# Sheet1.net
KiCad netlist of a schematic drawn in Altium Designer
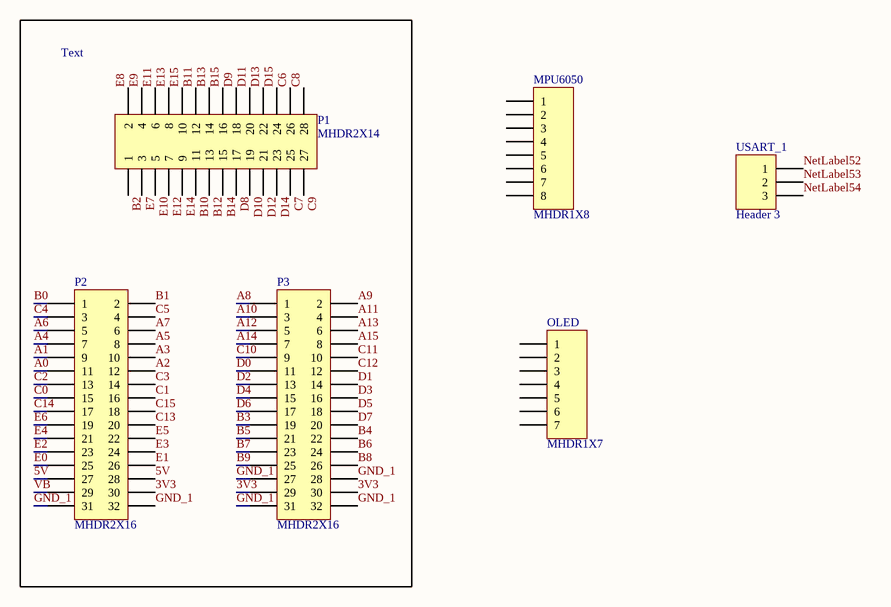
[diagram p0: Sheet1.SchDoc]

(export (version "E")
  (design (tool "Eeschema 10.0.6"))
  (components
    (comp (ref "MPU6050")
      (value "MHDR1X8")
      (footprint "MHDR1X8")
      (description "Header, 8-Pin")
      (fields (field (name "PUBLISHER") "Altium Limited"))
      (libsource (lib "Miscellaneous Connectors") (part "MHDR1X8"))
    )
    (comp (ref "OLED")
      (value "MHDR1X7")
      (footprint "MHDR1X7")
      (description "Header, 7-Pin")
      (fields (field (name "PUBLISHER") "Altium Limited"))
      (libsource (lib "Miscellaneous Connectors") (part "MHDR1X7"))
    )
    (comp (ref "P1")
      (value "MHDR2X14")
      (footprint "MHDR2X14")
      (description "Header, 14-Pin, Dual row")
      (fields (field (name "PUBLISHER") "Altium Limited"))
      (libsource (lib "Miscellaneous Connectors") (part "MHDR2X14"))
    )
    (comp (ref "P2")
      (value "MHDR2X16")
      (footprint "MHDR2X16")
      (description "Header, 16-Pin, Dual row")
      (fields (field (name "PUBLISHER") "Altium Limited"))
      (libsource (lib "Miscellaneous Connectors") (part "MHDR2X16"))
    )
    (comp (ref "P3")
      (value "MHDR2X16")
      (footprint "MHDR2X16")
      (description "Header, 16-Pin, Dual row")
      (fields (field (name "PUBLISHER") "Altium Limited"))
      (libsource (lib "Miscellaneous Connectors") (part "MHDR2X16"))
    )
    (comp (ref "USART_1")
      (value "Header 3")
      (footprint "HDR1X3")
      (description "Header, 3-Pin")
      (fields (field (name "PUBLISHER") "Altium Limited"))
      (libsource (lib "Miscellaneous Connectors") (part "Header 3"))
    )
  )
  (nets
    (net (code "1") (name "/3V3") (class "Default")
      (node (ref "P2") (pin "30") (pinfunction "30_30") (pintype "passive"))
      (node (ref "P3") (pin "29") (pinfunction "29_29") (pintype "passive"))
      (node (ref "P3") (pin "30") (pinfunction "30_30") (pintype "passive"))
    )
    (net (code "2") (name "/5V") (class "Default")
      (node (ref "P2") (pin "27") (pinfunction "27_27") (pintype "passive"))
      (node (ref "P2") (pin "28") (pinfunction "28_28") (pintype "passive"))
    )
    (net (code "3") (name "/A0") (class "Default")
      (node (ref "P2") (pin "11") (pinfunction "11_11") (pintype "passive"))
    )
    (net (code "4") (name "/A1") (class "Default")
      (node (ref "P2") (pin "9") (pinfunction "9_9") (pintype "passive"))
    )
    (net (code "5") (name "/A2") (class "Default")
      (node (ref "P2") (pin "12") (pinfunction "12_12") (pintype "passive"))
    )
    (net (code "6") (name "/A3") (class "Default")
      (node (ref "P2") (pin "10") (pinfunction "10_10") (pintype "passive"))
    )
    (net (code "7") (name "/A4") (class "Default")
      (node (ref "P2") (pin "7") (pinfunction "7_7") (pintype "passive"))
    )
    (net (code "8") (name "/A5") (class "Default")
      (node (ref "P2") (pin "8") (pinfunction "8_8") (pintype "passive"))
    )
    (net (code "9") (name "/A6") (class "Default")
      (node (ref "P2") (pin "5") (pinfunction "5_5") (pintype "passive"))
    )
    (net (code "10") (name "/A7") (class "Default")
      (node (ref "P2") (pin "6") (pinfunction "6_6") (pintype "passive"))
    )
    (net (code "11") (name "/A8") (class "Default")
      (node (ref "P3") (pin "1") (pinfunction "1_1") (pintype "passive"))
    )
    (net (code "12") (name "/A9") (class "Default")
      (node (ref "P3") (pin "2") (pinfunction "2_2") (pintype "passive"))
    )
    (net (code "13") (name "/A10") (class "Default")
      (node (ref "P3") (pin "3") (pinfunction "3_3") (pintype "passive"))
    )
    (net (code "14") (name "/A11") (class "Default")
      (node (ref "P3") (pin "4") (pinfunction "4_4") (pintype "passive"))
    )
    (net (code "15") (name "/A12") (class "Default")
      (node (ref "P3") (pin "5") (pinfunction "5_5") (pintype "passive"))
    )
    (net (code "16") (name "/A13") (class "Default")
      (node (ref "P3") (pin "6") (pinfunction "6_6") (pintype "passive"))
    )
    (net (code "17") (name "/A14") (class "Default")
      (node (ref "P3") (pin "7") (pinfunction "7_7") (pintype "passive"))
    )
    (net (code "18") (name "/A15") (class "Default")
      (node (ref "P3") (pin "8") (pinfunction "8_8") (pintype "passive"))
    )
    (net (code "19") (name "/B0") (class "Default")
      (node (ref "P2") (pin "1") (pinfunction "1_1") (pintype "passive"))
    )
    (net (code "20") (name "/B1") (class "Default")
      (node (ref "P2") (pin "2") (pinfunction "2_2") (pintype "passive"))
    )
    (net (code "21") (name "/B2") (class "Default")
      (node (ref "P1") (pin "1") (pinfunction "1_1") (pintype "passive"))
    )
    (net (code "22") (name "/B3") (class "Default")
      (node (ref "P3") (pin "19") (pinfunction "19_19") (pintype "passive"))
    )
    (net (code "23") (name "/B4") (class "Default")
      (node (ref "P3") (pin "22") (pinfunction "22_22") (pintype "passive"))
    )
    (net (code "24") (name "/B5") (class "Default")
      (node (ref "P3") (pin "21") (pinfunction "21_21") (pintype "passive"))
    )
    (net (code "25") (name "/B6") (class "Default")
      (node (ref "P3") (pin "24") (pinfunction "24_24") (pintype "passive"))
    )
    (net (code "26") (name "/B7") (class "Default")
      (node (ref "P3") (pin "23") (pinfunction "23_23") (pintype "passive"))
    )
    (net (code "27") (name "/B8") (class "Default")
      (node (ref "P3") (pin "26") (pinfunction "26_26") (pintype "passive"))
    )
    (net (code "28") (name "/B9") (class "Default")
      (node (ref "P3") (pin "25") (pinfunction "25_25") (pintype "passive"))
    )
    (net (code "29") (name "/B10") (class "Default")
      (node (ref "P1") (pin "11") (pinfunction "11_11") (pintype "passive"))
    )
    (net (code "30") (name "/B11") (class "Default")
      (node (ref "P1") (pin "12") (pinfunction "12_12") (pintype "passive"))
    )
    (net (code "31") (name "/B12") (class "Default")
      (node (ref "P1") (pin "13") (pinfunction "13_13") (pintype "passive"))
    )
    (net (code "32") (name "/B13") (class "Default")
      (node (ref "P1") (pin "14") (pinfunction "14_14") (pintype "passive"))
    )
    (net (code "33") (name "/B14") (class "Default")
      (node (ref "P1") (pin "15") (pinfunction "15_15") (pintype "passive"))
    )
    (net (code "34") (name "/B15") (class "Default")
      (node (ref "P1") (pin "16") (pinfunction "16_16") (pintype "passive"))
    )
    (net (code "35") (name "/C0") (class "Default")
      (node (ref "P2") (pin "15") (pinfunction "15_15") (pintype "passive"))
    )
    (net (code "36") (name "/C1") (class "Default")
      (node (ref "P2") (pin "16") (pinfunction "16_16") (pintype "passive"))
    )
    (net (code "37") (name "/C2") (class "Default")
      (node (ref "P2") (pin "13") (pinfunction "13_13") (pintype "passive"))
    )
    (net (code "38") (name "/C3") (class "Default")
      (node (ref "P2") (pin "14") (pinfunction "14_14") (pintype "passive"))
    )
    (net (code "39") (name "/C4") (class "Default")
      (node (ref "P2") (pin "3") (pinfunction "3_3") (pintype "passive"))
    )
    (net (code "40") (name "/C5") (class "Default")
      (node (ref "P2") (pin "4") (pinfunction "4_4") (pintype "passive"))
    )
    (net (code "41") (name "/C6") (class "Default")
      (node (ref "P1") (pin "26") (pinfunction "26_26") (pintype "passive"))
    )
    (net (code "42") (name "/C7") (class "Default")
      (node (ref "P1") (pin "25") (pinfunction "25_25") (pintype "passive"))
    )
    (net (code "43") (name "/C8") (class "Default")
      (node (ref "P1") (pin "28") (pinfunction "28_28") (pintype "passive"))
    )
    (net (code "44") (name "/C9") (class "Default")
      (node (ref "P1") (pin "27") (pinfunction "27_27") (pintype "passive"))
    )
    (net (code "45") (name "/C10") (class "Default")
      (node (ref "P3") (pin "9") (pinfunction "9_9") (pintype "passive"))
    )
    (net (code "46") (name "/C11") (class "Default")
      (node (ref "P3") (pin "10") (pinfunction "10_10") (pintype "passive"))
    )
    (net (code "47") (name "/C12") (class "Default")
      (node (ref "P3") (pin "12") (pinfunction "12_12") (pintype "passive"))
    )
    (net (code "48") (name "/C13") (class "Default")
      (node (ref "P2") (pin "20") (pinfunction "20_20") (pintype "passive"))
    )
    (net (code "49") (name "/C14") (class "Default")
      (node (ref "P2") (pin "17") (pinfunction "17_17") (pintype "passive"))
    )
    (net (code "50") (name "/C15") (class "Default")
      (node (ref "P2") (pin "18") (pinfunction "18_18") (pintype "passive"))
    )
    (net (code "51") (name "/D0") (class "Default")
      (node (ref "P3") (pin "11") (pinfunction "11_11") (pintype "passive"))
    )
    (net (code "52") (name "/D1") (class "Default")
      (node (ref "P3") (pin "14") (pinfunction "14_14") (pintype "passive"))
    )
    (net (code "53") (name "/D2") (class "Default")
      (node (ref "P3") (pin "13") (pinfunction "13_13") (pintype "passive"))
    )
    (net (code "54") (name "/D3") (class "Default")
      (node (ref "P3") (pin "16") (pinfunction "16_16") (pintype "passive"))
    )
    (net (code "55") (name "/D4") (class "Default")
      (node (ref "P3") (pin "15") (pinfunction "15_15") (pintype "passive"))
    )
    (net (code "56") (name "/D5") (class "Default")
      (node (ref "P3") (pin "18") (pinfunction "18_18") (pintype "passive"))
    )
    (net (code "57") (name "/D6") (class "Default")
      (node (ref "P3") (pin "17") (pinfunction "17_17") (pintype "passive"))
    )
    (net (code "58") (name "/D7") (class "Default")
      (node (ref "P3") (pin "20") (pinfunction "20_20") (pintype "passive"))
    )
    (net (code "59") (name "/D8") (class "Default")
      (node (ref "P1") (pin "17") (pinfunction "17_17") (pintype "passive"))
    )
    (net (code "60") (name "/D9") (class "Default")
      (node (ref "P1") (pin "18") (pinfunction "18_18") (pintype "passive"))
    )
    (net (code "61") (name "/D10") (class "Default")
      (node (ref "P1") (pin "19") (pinfunction "19_19") (pintype "passive"))
    )
    (net (code "62") (name "/D11") (class "Default")
      (node (ref "P1") (pin "20") (pinfunction "20_20") (pintype "passive"))
    )
    (net (code "63") (name "/D12") (class "Default")
      (node (ref "P1") (pin "21") (pinfunction "21_21") (pintype "passive"))
    )
    (net (code "64") (name "/D13") (class "Default")
      (node (ref "P1") (pin "22") (pinfunction "22_22") (pintype "passive"))
    )
    (net (code "65") (name "/D14") (class "Default")
      (node (ref "P1") (pin "23") (pinfunction "23_23") (pintype "passive"))
    )
    (net (code "66") (name "/D15") (class "Default")
      (node (ref "P1") (pin "24") (pinfunction "24_24") (pintype "passive"))
    )
    (net (code "67") (name "/E0") (class "Default")
      (node (ref "P2") (pin "25") (pinfunction "25_25") (pintype "passive"))
    )
    (net (code "68") (name "/E1") (class "Default")
      (node (ref "P2") (pin "26") (pinfunction "26_26") (pintype "passive"))
    )
    (net (code "69") (name "/E2") (class "Default")
      (node (ref "P2") (pin "23") (pinfunction "23_23") (pintype "passive"))
    )
    (net (code "70") (name "/E3") (class "Default")
      (node (ref "P2") (pin "24") (pinfunction "24_24") (pintype "passive"))
    )
    (net (code "71") (name "/E4") (class "Default")
      (node (ref "P2") (pin "21") (pinfunction "21_21") (pintype "passive"))
    )
    (net (code "72") (name "/E5") (class "Default")
      (node (ref "P2") (pin "22") (pinfunction "22_22") (pintype "passive"))
    )
    (net (code "73") (name "/E6") (class "Default")
      (node (ref "P2") (pin "19") (pinfunction "19_19") (pintype "passive"))
    )
    (net (code "74") (name "/E7") (class "Default")
      (node (ref "P1") (pin "3") (pinfunction "3_3") (pintype "passive"))
    )
    (net (code "75") (name "/E8") (class "Default")
      (node (ref "P1") (pin "2") (pinfunction "2_2") (pintype "passive"))
    )
    (net (code "76") (name "/E9") (class "Default")
      (node (ref "P1") (pin "4") (pinfunction "4_4") (pintype "passive"))
    )
    (net (code "77") (name "/E10") (class "Default")
      (node (ref "P1") (pin "5") (pinfunction "5_5") (pintype "passive"))
    )
    (net (code "78") (name "/E11") (class "Default")
      (node (ref "P1") (pin "6") (pinfunction "6_6") (pintype "passive"))
    )
    (net (code "79") (name "/E12") (class "Default")
      (node (ref "P1") (pin "7") (pinfunction "7_7") (pintype "passive"))
    )
    (net (code "80") (name "/E13") (class "Default")
      (node (ref "P1") (pin "8") (pinfunction "8_8") (pintype "passive"))
    )
    (net (code "81") (name "/E14") (class "Default")
      (node (ref "P1") (pin "9") (pinfunction "9_9") (pintype "passive"))
    )
    (net (code "82") (name "/E15") (class "Default")
      (node (ref "P1") (pin "10") (pinfunction "10_10") (pintype "passive"))
    )
    (net (code "83") (name "/GND_1") (class "Default")
      (node (ref "P2") (pin "31") (pinfunction "31_31") (pintype "passive"))
      (node (ref "P2") (pin "32") (pinfunction "32_32") (pintype "passive"))
      (node (ref "P3") (pin "27") (pinfunction "27_27") (pintype "passive"))
      (node (ref "P3") (pin "28") (pinfunction "28_28") (pintype "passive"))
      (node (ref "P3") (pin "31") (pinfunction "31_31") (pintype "passive"))
      (node (ref "P3") (pin "32") (pinfunction "32_32") (pintype "passive"))
    )
    (net (code "84") (name "/NetLabel52") (class "Default")
      (node (ref "USART_1") (pin "1") (pinfunction "1_1") (pintype "passive"))
    )
    (net (code "85") (name "/NetLabel53") (class "Default")
      (node (ref "USART_1") (pin "2") (pinfunction "2_2") (pintype "passive"))
    )
    (net (code "86") (name "/NetLabel54") (class "Default")
      (node (ref "USART_1") (pin "3") (pinfunction "3_3") (pintype "passive"))
    )
    (net (code "87") (name "/VB") (class "Default")
      (node (ref "P2") (pin "29") (pinfunction "29_29") (pintype "passive"))
    )
    (net (code "88") (name "unconnected-(MPU6050-Pad1)") (class "Default")
      (node (ref "MPU6050") (pin "1") (pinfunction "1_1") (pintype "passive"))
    )
    (net (code "89") (name "unconnected-(MPU6050-Pad2)") (class "Default")
      (node (ref "MPU6050") (pin "2") (pinfunction "2_2") (pintype "passive"))
    )
    (net (code "90") (name "unconnected-(MPU6050-Pad3)") (class "Default")
      (node (ref "MPU6050") (pin "3") (pinfunction "3_3") (pintype "passive"))
    )
    (net (code "91") (name "unconnected-(MPU6050-Pad4)") (class "Default")
      (node (ref "MPU6050") (pin "4") (pinfunction "4_4") (pintype "passive"))
    )
    (net (code "92") (name "unconnected-(MPU6050-Pad5)") (class "Default")
      (node (ref "MPU6050") (pin "5") (pinfunction "5_5") (pintype "passive"))
    )
    (net (code "93") (name "unconnected-(MPU6050-Pad6)") (class "Default")
      (node (ref "MPU6050") (pin "6") (pinfunction "6_6") (pintype "passive"))
    )
    (net (code "94") (name "unconnected-(MPU6050-Pad7)") (class "Default")
      (node (ref "MPU6050") (pin "7") (pinfunction "7_7") (pintype "passive"))
    )
    (net (code "95") (name "unconnected-(MPU6050-Pad8)") (class "Default")
      (node (ref "MPU6050") (pin "8") (pinfunction "8_8") (pintype "passive"))
    )
    (net (code "96") (name "unconnected-(OLED-Pad1)") (class "Default")
      (node (ref "OLED") (pin "1") (pinfunction "1_1") (pintype "passive"))
    )
    (net (code "97") (name "unconnected-(OLED-Pad2)") (class "Default")
      (node (ref "OLED") (pin "2") (pinfunction "2_2") (pintype "passive"))
    )
    (net (code "98") (name "unconnected-(OLED-Pad3)") (class "Default")
      (node (ref "OLED") (pin "3") (pinfunction "3_3") (pintype "passive"))
    )
    (net (code "99") (name "unconnected-(OLED-Pad4)") (class "Default")
      (node (ref "OLED") (pin "4") (pinfunction "4_4") (pintype "passive"))
    )
    (net (code "100") (name "unconnected-(OLED-Pad5)") (class "Default")
      (node (ref "OLED") (pin "5") (pinfunction "5_5") (pintype "passive"))
    )
    (net (code "101") (name "unconnected-(OLED-Pad6)") (class "Default")
      (node (ref "OLED") (pin "6") (pinfunction "6_6") (pintype "passive"))
    )
    (net (code "102") (name "unconnected-(OLED-Pad7)") (class "Default")
      (node (ref "OLED") (pin "7") (pinfunction "7_7") (pintype "passive"))
    )
  )
)
